# Power_Circuitry.net
KiCad netlist of a schematic drawn in Altium Designer
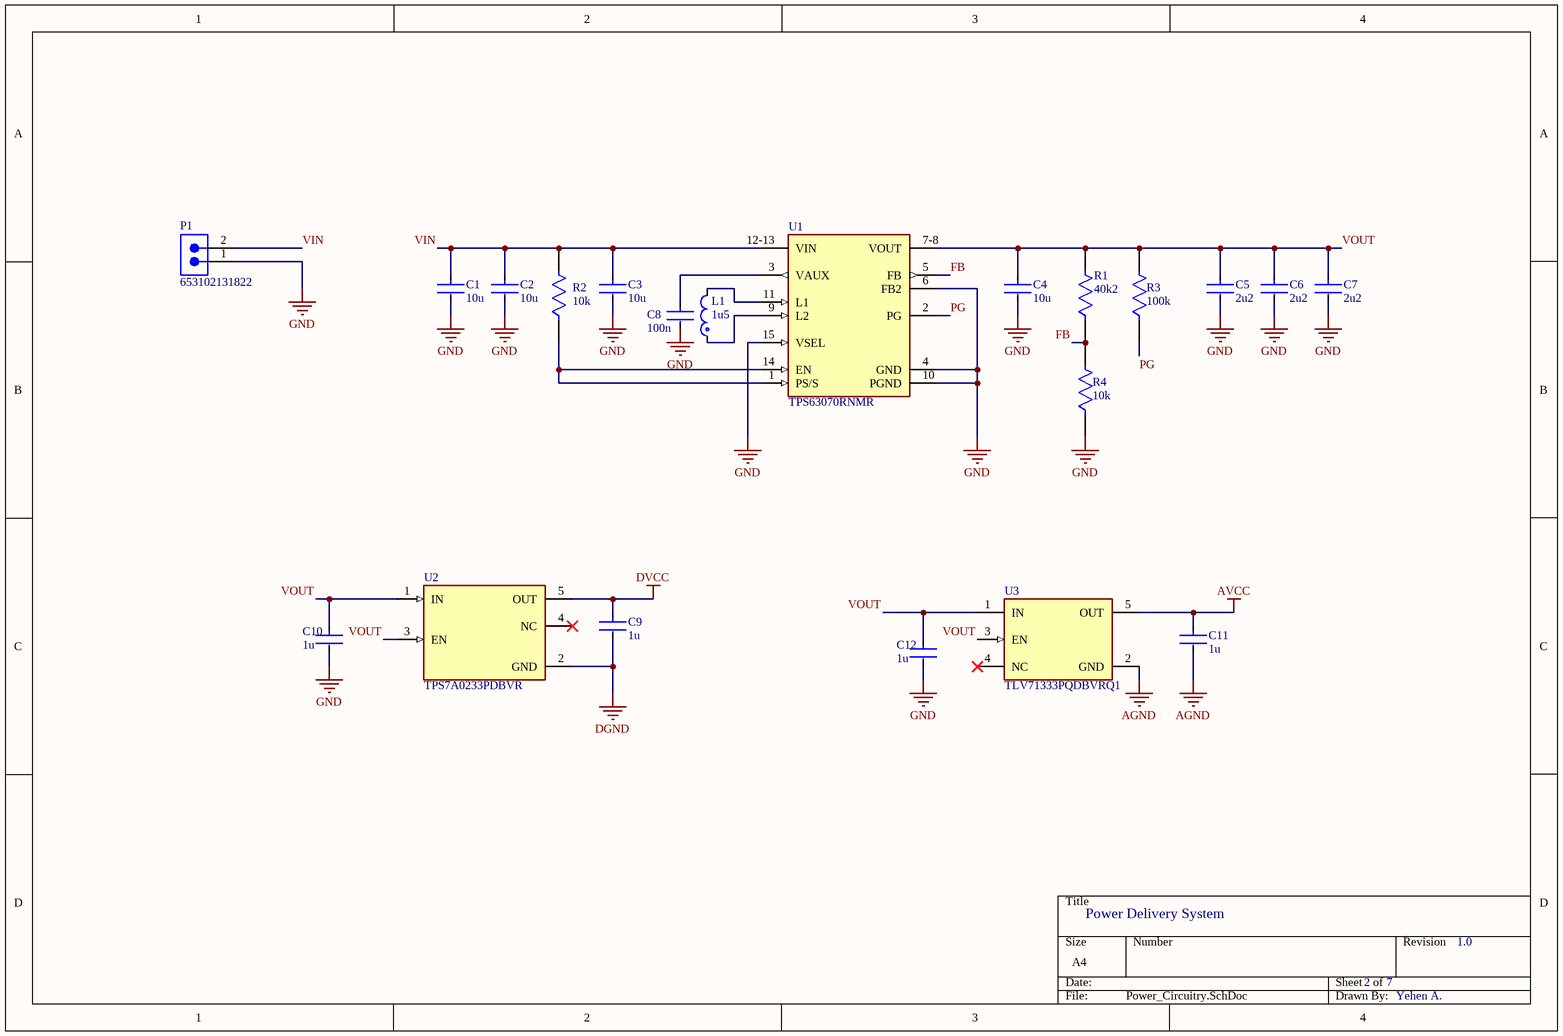
[diagram p0: Power_Circuitry.SchDoc]

(export (version "E")
  (design (tool "Eeschema 10.0.6"))
  (components
    (comp (ref "C1")
      (value "10u")
      (footprint "FP-GRM21B-0_2-e0_2_0_7-IPC_C")
      (description "Chip Multilayer Ceramic Capacitors for General Purpose, 0805, 10uF, X7S, 22%, 20%, 25V")
      (fields (field (name "TOLERANCE") "20%"))
      (libsource (lib "Altium Content Vault") (part "b4654b650e69147ec39a6b967a45e02"))
    )
    (comp (ref "C2")
      (value "10u")
      (footprint "FP-GRM21B-0_2-e0_2_0_7-IPC_C")
      (description "Chip Multilayer Ceramic Capacitors for General Purpose, 0805, 10uF, X7S, 22%, 20%, 25V")
      (fields (field (name "TOLERANCE") "20%"))
      (libsource (lib "Altium Content Vault") (part "b4654b650e69147ec39a6b967a45e02"))
    )
    (comp (ref "C3")
      (value "10u")
      (footprint "FP-GRM21B-0_2-e0_2_0_7-IPC_C")
      (description "Chip Multilayer Ceramic Capacitors for General Purpose, 0805, 10uF, X7S, 22%, 20%, 25V")
      (fields (field (name "TOLERANCE") "20%"))
      (libsource (lib "Altium Content Vault") (part "b4654b650e69147ec39a6b967a45e02"))
    )
    (comp (ref "C4")
      (value "10u")
      (footprint "FP-GRM21B-0_2-e0_2_0_7-IPC_C")
      (description "Chip Multilayer Ceramic Capacitors for General Purpose, 0805, 10uF, X7S, 22%, 20%, 25V")
      (fields (field (name "TOLERANCE") "20%"))
      (libsource (lib "Altium Content Vault") (part "b4654b650e69147ec39a6b967a45e02"))
    )
    (comp (ref "C5")
      (value "2u2")
      (footprint "FP-GRM21B-0_2-e0_2_0_7-IPC_B")
      (description "CAP CER 2.2UF 100V X7T 0805")
      (libsource (lib "Altium Content Vault") (part "b4654b650e69147ec39a6b967a45e02"))
    )
    (comp (ref "C6")
      (value "2u2")
      (footprint "FP-GRM21B-0_2-e0_2_0_7-IPC_B")
      (description "CAP CER 2.2UF 100V X7T 0805")
      (libsource (lib "Altium Content Vault") (part "b4654b650e69147ec39a6b967a45e02"))
    )
    (comp (ref "C7")
      (value "2u2")
      (footprint "FP-GRM21B-0_2-e0_2_0_7-IPC_B")
      (description "CAP CER 2.2UF 100V X7T 0805")
      (libsource (lib "Altium Content Vault") (part "b4654b650e69147ec39a6b967a45e02"))
    )
    (comp (ref "C8")
      (value "100n")
      (footprint "FP-GRM155-0_05-MFG")
      (description "Chip Multilayer Ceramic Capacitors for General Purpose, 0402, 0.10uF, B, 10%, 20%, 50V")
      (libsource (lib "Altium Content Vault") (part "02cd4be3c70576c341d710602a673aa"))
    )
    (comp (ref "C9")
      (value "1u")
      (footprint "FP-0603-L_1_6_0_15-W_0_81-IPC_C")
      (description "General Purpose Ceramic Capacitor, 0603, 1uF, 10%, X5R, 15%, 6.3V")
      (fields (field (name "VOLTAGE") "6.3V") (field (name "TOLERANCE") "10%"))
      (libsource (lib "Altium Content Vault") (part "02cd4be3c70576c341d710602a673aa"))
    )
    (comp (ref "C10")
      (value "1u")
      (footprint "FP-0603-L_1_6_0_15-W_0_81-IPC_C")
      (description "General Purpose Ceramic Capacitor, 0603, 1uF, 10%, X5R, 15%, 6.3V")
      (fields (field (name "VOLTAGE") "6.3V") (field (name "TOLERANCE") "10%"))
      (libsource (lib "Altium Content Vault") (part "02cd4be3c70576c341d710602a673aa"))
    )
    (comp (ref "C11")
      (value "1u")
      (footprint "FP-0603-L_1_6_0_15-W_0_81-IPC_C")
      (description "General Purpose Ceramic Capacitor, 0603, 1uF, 10%, X5R, 15%, 6.3V")
      (fields (field (name "VOLTAGE") "6.3V") (field (name "TOLERANCE") "10%"))
      (libsource (lib "Altium Content Vault") (part "02cd4be3c70576c341d710602a673aa"))
    )
    (comp (ref "C12")
      (value "1u")
      (footprint "FP-0603-L_1_6_0_15-W_0_81-IPC_C")
      (description "General Purpose Ceramic Capacitor, 0603, 1uF, 10%, X5R, 15%, 6.3V")
      (fields (field (name "VOLTAGE") "6.3V") (field (name "TOLERANCE") "10%"))
      (libsource (lib "Altium Content Vault") (part "02cd4be3c70576c341d710602a673aa"))
    )
    (comp (ref "L1")
      (value "1u5")
      (footprint "FP-XFL4020-MFG")
      (fields (field (name "TOLERANCE") "20%"))
      (libsource (lib "Altium Content Vault") (part "4cc4b267dca4c8e51f7102f422741d8"))
    )
    (comp (ref "P1")
      (value "653102131822")
      (footprint "653102131822")
      (libsource (lib "Altium Content Vault") (part "Header_Male_1R_02P"))
    )
    (comp (ref "R1")
      (value "40k2")
      (footprint "FP-RN732A-MFG")
      (description "SMD Chip Resistor, Thin Film, 40.2KΩ, 100 V, 0805 [2012 Metric], 100 mW, 0.1%, RN73 Series")
      (fields
        (field (name "OCTOPART") "https://octopart.com/rn73c2a40k2btdf-te+connectivity-21411991")
        (field (name "TOLERANCE") "0.1%")
      )
      (libsource (lib "Altium Content Vault") (part "1029c3af85768c4190bb7ad29bc67b5"))
    )
    (comp (ref "R2")
      (value "10k")
      (footprint "FP-CRGCQ0805-IPC_C")
      (description "CRGCQ 0805 10K 5%")
      (fields
        (field (name "MANUFACTURER PART NUMBER") "CRGCQ0805J10K")
        (field (name "MANUFACTURER") "TE Connectivity")
      )
      (libsource (lib "Altium Content Vault") (part "1029c3af85768c4190bb7ad29bc67b5"))
    )
    (comp (ref "R3")
      (value "100k")
      (footprint "FP-RN732A-MFG")
      (description "SMD Chip Resistor, Thin Film, 100KΩ, 100 V, 0805 [2012 Metric], 100 mW, 0.1%, RN73 Series")
      (fields
        (field (name "MANUFACTURER PART NUMBER") "RN73C2A100KB")
        (field (name "OCTOPART") "https://octopart.com/rn73c2a100kb-te+connectivity-16078029")
      )
      (libsource (lib "Altium Content Vault") (part "1029c3af85768c4190bb7ad29bc67b5"))
    )
    (comp (ref "R4")
      (value "10k")
      (footprint "FP-RN732A-MFG")
      (description "SMD Chip Resistor, Thin Film, 10KΩ, 100 V, 0805 [2012 Metric], 100 mW, 0.1%, RN73 Series")
      (fields
        (field (name "MANUFACTURER PART NUMBER") "RN73C2A10KBTG")
        (field (name "MANUFACTURER") "TE Connectivity")
      )
      (libsource (lib "Altium Content Vault") (part "1029c3af85768c4190bb7ad29bc67b5"))
    )
    (comp (ref "U1")
      (value "TPS63070RNMR")
      (footprint "FP-RNM0015A-MFG")
      (description "IC REG BCK BST ADJ 3.6A 15VQFN")
      (libsource (lib "Altium Content Vault") (part "a4d5b1e6901c8533e317c4aea8f1b15"))
    )
    (comp (ref "U2")
      (value "TPS7A0233PDBVR")
      (footprint "FP-DBV0005A-IPC_B")
      (description "IC REG LINEAR 3.3V 200MA SOT23-5")
      (libsource (lib "Altium Content Vault") (part "3122ecd2a83b5a5c9ac358189361456"))
    )
    (comp (ref "U3")
      (value "TLV71333PQDBVRQ1")
      (footprint "FP-DBV0005A-IPC_C")
      (description "IC REG LINEAR 3.3V 150MA SOT23-5")
      (libsource (lib "Altium Content Vault") (part "66ca6db733a9cb813c480efc7723418"))
    )
  )
  (nets
    (net (code "1") (name "/FB") (class "Default")
      (node (ref "R1") (pin "1") (pinfunction "1_1") (pintype "passive"))
      (node (ref "R4") (pin "2") (pinfunction "2_2") (pintype "passive"))
      (node (ref "U1") (pin "5") (pinfunction "FB_5") (pintype "output"))
    )
    (net (code "2") (name "/PG") (class "Default")
      (node (ref "R3") (pin "1") (pinfunction "1_1") (pintype "passive"))
      (node (ref "U1") (pin "2") (pinfunction "PG_2") (pintype "open_collector"))
    )
    (net (code "3") (name "/VIN") (class "Default")
      (node (ref "C1") (pin "1") (pinfunction "1_1") (pintype "passive"))
      (node (ref "C2") (pin "1") (pinfunction "1_1") (pintype "passive"))
      (node (ref "C3") (pin "1") (pinfunction "1_1") (pintype "passive"))
      (node (ref "P1") (pin "2") (pinfunction "2_2") (pintype "passive"))
      (node (ref "R2") (pin "2") (pinfunction "2_2") (pintype "passive"))
      (node (ref "U1") (pin "12-13") (pinfunction "VIN_12-13") (pintype "power_in"))
    )
    (net (code "4") (name "/VOUT") (class "Default")
      (node (ref "C10") (pin "1") (pinfunction "1_1") (pintype "passive"))
      (node (ref "C12") (pin "1") (pinfunction "1_1") (pintype "passive"))
      (node (ref "C4") (pin "1") (pinfunction "1_1") (pintype "passive"))
      (node (ref "C5") (pin "1") (pinfunction "1_1") (pintype "passive"))
      (node (ref "C6") (pin "1") (pinfunction "1_1") (pintype "passive"))
      (node (ref "C7") (pin "1") (pinfunction "1_1") (pintype "passive"))
      (node (ref "R1") (pin "2") (pinfunction "2_2") (pintype "passive"))
      (node (ref "R3") (pin "2") (pinfunction "2_2") (pintype "passive"))
      (node (ref "U1") (pin "7-8") (pinfunction "VOUT_7-8") (pintype "passive"))
      (node (ref "U2") (pin "1") (pinfunction "IN_1") (pintype "input"))
      (node (ref "U2") (pin "3") (pinfunction "EN_3") (pintype "input"))
      (node (ref "U3") (pin "1") (pinfunction "IN_1") (pintype "power_in"))
      (node (ref "U3") (pin "3") (pinfunction "EN_3") (pintype "input"))
    )
    (net (code "5") (name "AGND") (class "Default")
      (node (ref "C11") (pin "2") (pinfunction "2_2") (pintype "passive"))
      (node (ref "U3") (pin "2") (pinfunction "GND_2") (pintype "power_in"))
    )
    (net (code "6") (name "AVCC") (class "Default")
      (node (ref "C11") (pin "1") (pinfunction "1_1") (pintype "passive"))
      (node (ref "U3") (pin "5") (pinfunction "OUT_5") (pintype "power_in"))
    )
    (net (code "7") (name "DGND") (class "Default")
      (node (ref "C9") (pin "2") (pinfunction "2_2") (pintype "passive"))
      (node (ref "U2") (pin "2") (pinfunction "GND_2") (pintype "power_in"))
    )
    (net (code "8") (name "DVCC") (class "Default")
      (node (ref "C9") (pin "1") (pinfunction "1_1") (pintype "passive"))
      (node (ref "U2") (pin "5") (pinfunction "OUT_5") (pintype "passive"))
    )
    (net (code "9") (name "GND") (class "Default")
      (node (ref "C1") (pin "2") (pinfunction "2_2") (pintype "passive"))
      (node (ref "C10") (pin "2") (pinfunction "2_2") (pintype "passive"))
      (node (ref "C12") (pin "2") (pinfunction "2_2") (pintype "passive"))
      (node (ref "C2") (pin "2") (pinfunction "2_2") (pintype "passive"))
      (node (ref "C3") (pin "2") (pinfunction "2_2") (pintype "passive"))
      (node (ref "C4") (pin "2") (pinfunction "2_2") (pintype "passive"))
      (node (ref "C5") (pin "2") (pinfunction "2_2") (pintype "passive"))
      (node (ref "C6") (pin "2") (pinfunction "2_2") (pintype "passive"))
      (node (ref "C7") (pin "2") (pinfunction "2_2") (pintype "passive"))
      (node (ref "C8") (pin "2") (pinfunction "2_2") (pintype "passive"))
      (node (ref "P1") (pin "1") (pinfunction "1_1") (pintype "passive"))
      (node (ref "R4") (pin "1") (pinfunction "1_1") (pintype "passive"))
      (node (ref "U1") (pin "10") (pinfunction "PGND_10") (pintype "passive"))
      (node (ref "U1") (pin "15") (pinfunction "VSEL_15") (pintype "input"))
      (node (ref "U1") (pin "4") (pinfunction "GND_4") (pintype "passive"))
      (node (ref "U1") (pin "6") (pinfunction "FB2_6") (pintype "passive"))
    )
    (net (code "10") (name "Net-(U1-EN)") (class "Default")
      (node (ref "R2") (pin "1") (pinfunction "1_1") (pintype "passive"))
      (node (ref "U1") (pin "1") (pinfunction "PS/S_1") (pintype "input"))
      (node (ref "U1") (pin "14") (pinfunction "EN_14") (pintype "input"))
    )
    (net (code "11") (name "Net-(U1-L1)") (class "Default")
      (node (ref "L1") (pin "2") (pinfunction "2_2") (pintype "passive"))
      (node (ref "U1") (pin "11") (pinfunction "L1_11") (pintype "input"))
    )
    (net (code "12") (name "Net-(U1-L2)") (class "Default")
      (node (ref "L1") (pin "1") (pinfunction "1_1") (pintype "passive"))
      (node (ref "U1") (pin "9") (pinfunction "L2_9") (pintype "input"))
    )
    (net (code "13") (name "Net-(U1-VAUX)") (class "Default")
      (node (ref "C8") (pin "1") (pinfunction "1_1") (pintype "passive"))
      (node (ref "U1") (pin "3") (pinfunction "VAUX_3") (pintype "output"))
    )
    (net (code "14") (name "unconnected-(U2-NC-Pad4)") (class "Default")
      (node (ref "U2") (pin "4") (pinfunction "NC_4") (pintype "passive+no_connect"))
    )
    (net (code "15") (name "unconnected-(U3-NC-Pad4)") (class "Default")
      (node (ref "U3") (pin "4") (pinfunction "NC_4") (pintype "passive+no_connect"))
    )
  )
)
